# UART.net
KiCad netlist of a schematic drawn in Altium Designer
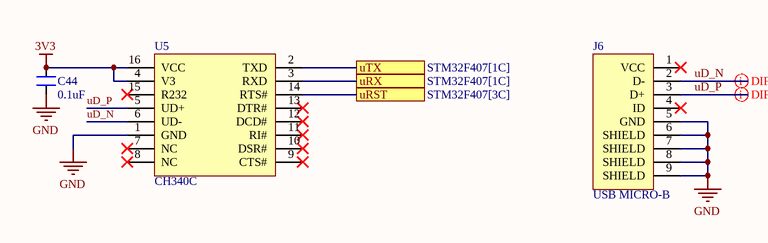
[diagram p0: UART.SchDoc]

(export (version "E")
  (design (tool "Eeschema 10.0.6"))
  (components
    (comp (ref "C44")
      (value "0.1uF")
      (footprint "CAP_0805")
      (description "0.1µF ±5% 50V Ceramic Capacitor X7R 0805 (2012 Metric)")
      (fields
        (field (name "MANUFACTURER") "AVX Corporation")
        (field (name "MANUFACTURER PART NUMBER") "08055C104JAT4A")
      )
      (libsource (lib "ESTEEMPCBLIB") (part "CAP_0.1uF-50V-5%-0805"))
    )
    (comp (ref "J6")
      (value "USB MICRO-B")
      (footprint "CON_10118192-0001LF_SMD")
      (description "USB - micro B USB 2.0 Receptacle Connector 5 Position Surface Mount, Right Angle")
      (fields (field (name "MANUFACTURER") "ICC") (field (name "MANUFACTURER PART NUMBER") "10118192-0001LF"))
      (libsource (lib "ESTEEMPCBLIB") (part "CON_USB2.0_MICROB-SMD"))
    )
    (comp (ref "U5")
      (value "CH340C")
      (footprint "SOIC16_50_284_25X90_SMT")
      (description "USB Bridge, USB to UART USB 2.0 UART Interface")
      (fields (field (name "MANUFACTURER") "Olimex"))
      (libsource (lib "ESTEEMPCBLIB") (part "IC_CH340C"))
    )
  )
  (nets
    (net (code "1") (name "/uD_N") (class "Default")
      (node (ref "J6") (pin "2") (pinfunction "D-_2") (pintype "passive"))
      (node (ref "U5") (pin "6") (pinfunction "UD-_6") (pintype "passive"))
    )
    (net (code "2") (name "/uD_P") (class "Default")
      (node (ref "J6") (pin "3") (pinfunction "D+_3") (pintype "passive"))
      (node (ref "U5") (pin "5") (pinfunction "UD+_5") (pintype "passive"))
    )
    (net (code "3") (name "/uRST") (class "Default")
      (node (ref "U5") (pin "14") (pinfunction "RTS#_14") (pintype "passive"))
    )
    (net (code "4") (name "/uRX") (class "Default")
      (node (ref "U5") (pin "3") (pinfunction "RXD_3") (pintype "passive"))
    )
    (net (code "5") (name "/uTX") (class "Default")
      (node (ref "U5") (pin "2") (pinfunction "TXD_2") (pintype "passive"))
    )
    (net (code "6") (name "3V3") (class "Default")
      (node (ref "C44") (pin "2") (pinfunction "2_2") (pintype "passive"))
      (node (ref "U5") (pin "16") (pinfunction "VCC_16") (pintype "passive"))
      (node (ref "U5") (pin "4") (pinfunction "V3_4") (pintype "passive"))
    )
    (net (code "7") (name "GND") (class "Default")
      (node (ref "C44") (pin "1") (pinfunction "1_1") (pintype "passive"))
      (node (ref "J6") (pin "5") (pinfunction "GND_5") (pintype "passive"))
      (node (ref "J6") (pin "6") (pinfunction "SHIELD_6") (pintype "passive"))
      (node (ref "J6") (pin "7") (pinfunction "SHIELD_7") (pintype "passive"))
      (node (ref "J6") (pin "8") (pinfunction "SHIELD_8") (pintype "passive"))
      (node (ref "J6") (pin "9") (pinfunction "SHIELD_9") (pintype "passive"))
      (node (ref "U5") (pin "1") (pinfunction "GND_1") (pintype "passive"))
    )
    (net (code "8") (name "unconnected-(J6-ID-Pad4)") (class "Default")
      (node (ref "J6") (pin "4") (pinfunction "ID_4") (pintype "passive+no_connect"))
    )
    (net (code "9") (name "unconnected-(J6-VCC-Pad1)") (class "Default")
      (node (ref "J6") (pin "1") (pinfunction "VCC_1") (pintype "passive+no_connect"))
    )
    (net (code "10") (name "unconnected-(U5-CTS#-Pad9)") (class "Default")
      (node (ref "U5") (pin "9") (pinfunction "CTS#_9") (pintype "passive+no_connect"))
    )
    (net (code "11") (name "unconnected-(U5-DCD#-Pad12)") (class "Default")
      (node (ref "U5") (pin "12") (pinfunction "DCD#_12") (pintype "passive+no_connect"))
    )
    (net (code "12") (name "unconnected-(U5-DSR#-Pad10)") (class "Default")
      (node (ref "U5") (pin "10") (pinfunction "DSR#_10") (pintype "passive+no_connect"))
    )
    (net (code "13") (name "unconnected-(U5-DTR#-Pad13)") (class "Default")
      (node (ref "U5") (pin "13") (pinfunction "DTR#_13") (pintype "passive+no_connect"))
    )
    (net (code "14") (name "unconnected-(U5-NC-Pad7)") (class "Default")
      (node (ref "U5") (pin "7") (pinfunction "NC_7") (pintype "passive+no_connect"))
    )
    (net (code "15") (name "unconnected-(U5-NC-Pad8)") (class "Default")
      (node (ref "U5") (pin "8") (pinfunction "NC_8") (pintype "passive+no_connect"))
    )
    (net (code "16") (name "unconnected-(U5-R232-Pad15)") (class "Default")
      (node (ref "U5") (pin "15") (pinfunction "R232_15") (pintype "passive+no_connect"))
    )
    (net (code "17") (name "unconnected-(U5-RI#-Pad11)") (class "Default")
      (node (ref "U5") (pin "11") (pinfunction "RI#_11") (pintype "passive+no_connect"))
    )
  )
)
